# LoopV2_6.net
KiCad netlist of a schematic drawn in EAGLE
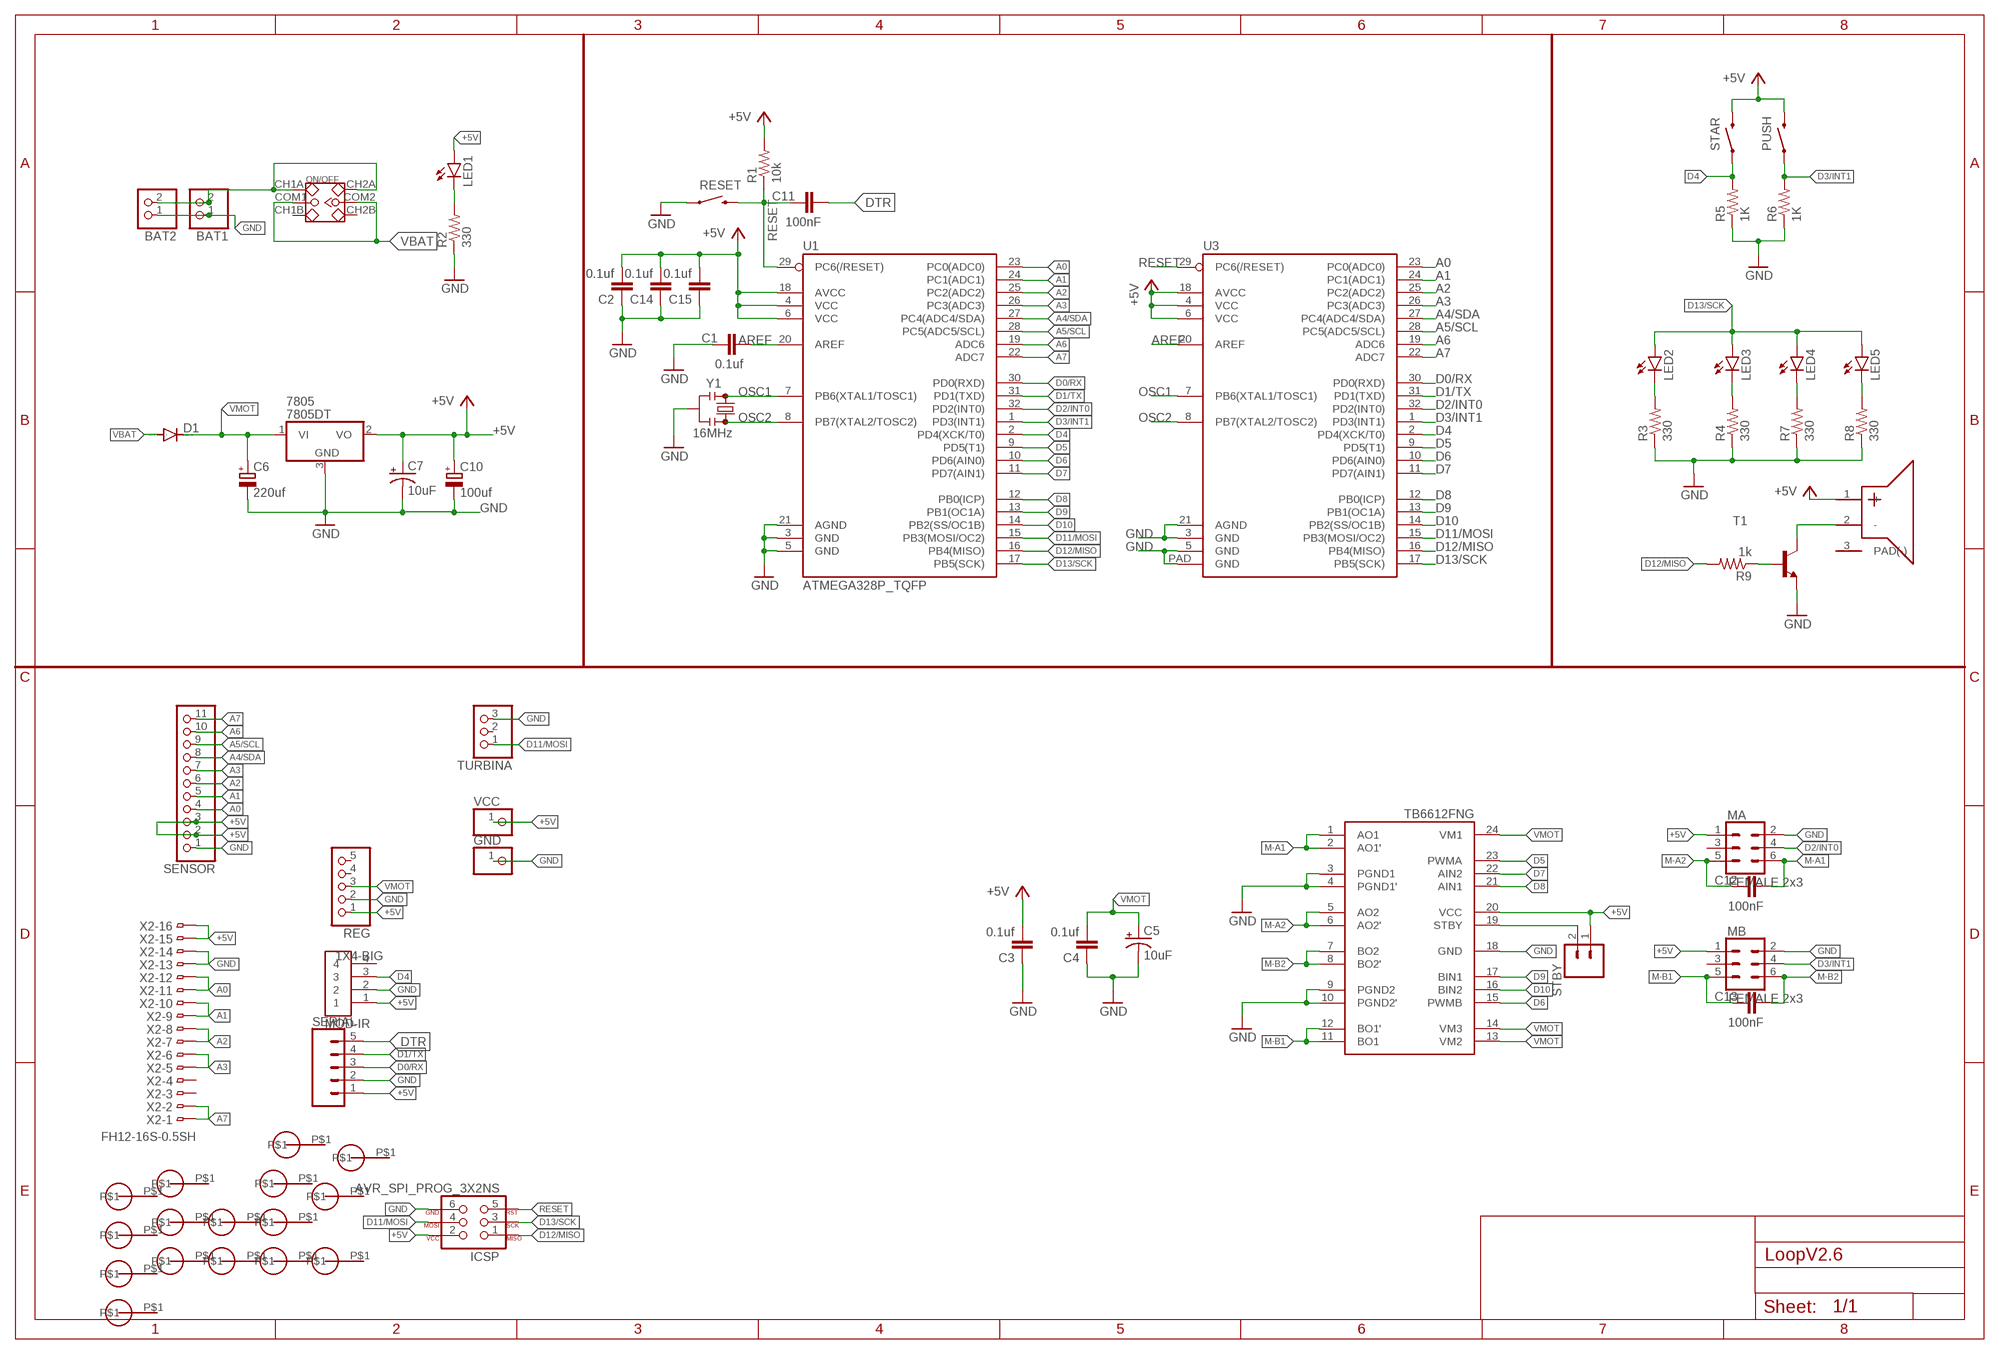
[diagram p0: schematic, sheet 1]

(export (version "E")
  (design (tool "Eeschema 10.0.6"))
  (components
    (comp (ref "7805")
      (value "7805DT")
      (footprint "eagle-import:TO252")
      (libsource (lib "eagle-import") (part "78DT05"))
    )
    (comp (ref "BAT1")
      (value "PINHD-1X2")
      (footprint "eagle-import:1X02")
      (libsource (lib "eagle-import") (part "PINHD-1X2"))
    )
    (comp (ref "BAT2")
      (value "PINHD-1X2")
      (footprint "eagle-import:1X02")
      (libsource (lib "eagle-import") (part "PINHD-1X2"))
    )
    (comp (ref "C1")
      (value "0.1uf")
      (footprint "eagle-import:C0805K")
      (libsource (lib "eagle-import") (part "C-EUC0805K"))
    )
    (comp (ref "C2")
      (value "0.1uf")
      (footprint "eagle-import:C0805K")
      (libsource (lib "eagle-import") (part "C-EUC0805K"))
    )
    (comp (ref "C3")
      (value "0.1uf")
      (footprint "eagle-import:C0805K")
      (libsource (lib "eagle-import") (part "C-EUC0805K"))
    )
    (comp (ref "C4")
      (value "0.1uf")
      (footprint "eagle-import:C0805K")
      (libsource (lib "eagle-import") (part "C-EUC0805K"))
    )
    (comp (ref "C5")
      (value "10uF")
      (footprint "eagle-import:EIA3216")
      (libsource (lib "eagle-import") (part "10UF-POLAR-EIA3216-16V-10%(TANT)"))
    )
    (comp (ref "C6")
      (value "220uf")
      (footprint "eagle-import:175TMP-0808")
      (libsource (lib "eagle-import") (part "CPOL-EU175TMP-0808"))
    )
    (comp (ref "C7")
      (value "10uF")
      (footprint "eagle-import:EIA3216")
      (libsource (lib "eagle-import") (part "10UF-POLAR-EIA3216-16V-10%(TANT)"))
    )
    (comp (ref "C10")
      (value "100uf")
      (footprint "eagle-import:153CLV-0605")
      (libsource (lib "eagle-import") (part "CPOL-EU153CLV-0605"))
    )
    (comp (ref "C11")
      (value "100nF")
      (footprint "eagle-import:C0805K")
      (libsource (lib "eagle-import") (part "C-EUC0805K"))
    )
    (comp (ref "C12")
      (value "100nF")
      (footprint "eagle-import:C0805K")
      (libsource (lib "eagle-import") (part "C-EUC0805K"))
    )
    (comp (ref "C13")
      (value "100nF")
      (footprint "eagle-import:C0805K")
      (libsource (lib "eagle-import") (part "C-EUC0805K"))
    )
    (comp (ref "C14")
      (value "0.1uf")
      (footprint "eagle-import:C0805K")
      (libsource (lib "eagle-import") (part "C-EUC0805K"))
    )
    (comp (ref "C15")
      (value "0.1uf")
      (footprint "eagle-import:C0805K")
      (libsource (lib "eagle-import") (part "C-EUC0805K"))
    )
    (comp (ref "D1")
      (value "DIODE-DO214AA")
      (footprint "eagle-import:DO214AA")
      (libsource (lib "eagle-import") (part "DIODE-DO214AA"))
    )
    (comp (ref "GND")
      (value "PINHD-1X1CB")
      (footprint "eagle-import:1X01-CLEANBIG")
      (libsource (lib "eagle-import") (part "PINHD-1X1CB"))
    )
    (comp (ref "IC1")
      (value "TB6612FNG")
      (footprint "eagle-import:SSOP24")
      (libsource (lib "eagle-import") (part "TB6612FNG"))
    )
    (comp (ref "ICSP")
      (value "AVR_SPI_PROG_3X2NS")
      (footprint "eagle-import:2X3-NS")
      (libsource (lib "eagle-import") (part "AVR_SPI_PROG_3X2NS"))
    )
    (comp (ref "LED1")
      (value "LEDCHIPLED_0805")
      (footprint "eagle-import:CHIPLED_0805")
      (libsource (lib "eagle-import") (part "LEDCHIPLED_0805"))
    )
    (comp (ref "LED2")
      (value "LEDCHIPLED_0805")
      (footprint "eagle-import:CHIPLED_0805")
      (libsource (lib "eagle-import") (part "LEDCHIPLED_0805"))
    )
    (comp (ref "LED3")
      (value "LEDCHIPLED_0805")
      (footprint "eagle-import:CHIPLED_0805")
      (libsource (lib "eagle-import") (part "LEDCHIPLED_0805"))
    )
    (comp (ref "LED4")
      (value "LEDCHIPLED_0805")
      (footprint "eagle-import:CHIPLED_0805")
      (libsource (lib "eagle-import") (part "LEDCHIPLED_0805"))
    )
    (comp (ref "LED5")
      (value "LEDCHIPLED_0805")
      (footprint "eagle-import:CHIPLED_0805")
      (libsource (lib "eagle-import") (part "LEDCHIPLED_0805"))
    )
    (comp (ref "MA")
      (value "FEMALE 2x3")
      (footprint "eagle-import:2X3")
      (libsource (lib "eagle-import") (part "CONN_03X2FEMALE"))
    )
    (comp (ref "MB")
      (value "FEMALE 2x3")
      (footprint "eagle-import:2X3")
      (libsource (lib "eagle-import") (part "CONN_03X2FEMALE"))
    )
    (comp (ref "MOD-IR")
      (value "1X4-BIG")
      (footprint "eagle-import:1X04-BIG")
      (libsource (lib "eagle-import") (part "1X4-BIG"))
    )
    (comp (ref "ON/OFF")
      (value "SWITCH-8.53.5MM-THT")
      (footprint "eagle-import:SWITCH-8.5_3.5MM-THT")
      (fields (field (name "MPN") "MS-22D18 G2 ROHS"))
      (libsource (lib "eagle-import") (part "SWITCH-8.53.5MM-THT"))
    )
    (comp (ref "PUSH")
      (value "TESTING_SWITCH-MOMENTARY-2SMD")
      (footprint "eagle-import:TESTING_TACTILE_SWITCH_SMD")
      (libsource (lib "eagle-import") (part "TESTING_SWITCH-MOMENTARY-2SMD"))
    )
    (comp (ref "R1")
      (value "10k")
      (footprint "eagle-import:R0805")
      (libsource (lib "eagle-import") (part "R-US_R0805"))
    )
    (comp (ref "R2")
      (value "330")
      (footprint "eagle-import:R0805")
      (libsource (lib "eagle-import") (part "R-US_R0805"))
    )
    (comp (ref "R3")
      (value "330")
      (footprint "eagle-import:R0805")
      (libsource (lib "eagle-import") (part "R-US_R0805"))
    )
    (comp (ref "R4")
      (value "330")
      (footprint "eagle-import:R0805")
      (libsource (lib "eagle-import") (part "R-US_R0805"))
    )
    (comp (ref "R5")
      (value "1K")
      (footprint "eagle-import:R0805")
      (libsource (lib "eagle-import") (part "R-US_R0805"))
    )
    (comp (ref "R6")
      (value "1K")
      (footprint "eagle-import:R0805")
      (libsource (lib "eagle-import") (part "R-US_R0805"))
    )
    (comp (ref "R7")
      (value "330")
      (footprint "eagle-import:R0805")
      (libsource (lib "eagle-import") (part "R-US_R0805"))
    )
    (comp (ref "R8")
      (value "330")
      (footprint "eagle-import:R0805")
      (libsource (lib "eagle-import") (part "R-US_R0805"))
    )
    (comp (ref "R9")
      (value "1k")
      (footprint "eagle-import:R0805")
      (libsource (lib "eagle-import") (part "R-US_R0805"))
    )
    (comp (ref "REG")
      (value "PINHD-1X5")
      (footprint "eagle-import:1X05")
      (libsource (lib "eagle-import") (part "PINHD-1X5"))
    )
    (comp (ref "RESET")
      (value "TESTING_SWITCH-MOMENTARY-2SMD")
      (footprint "eagle-import:TESTING_TACTILE_SWITCH_SMD")
      (libsource (lib "eagle-import") (part "TESTING_SWITCH-MOMENTARY-2SMD"))
    )
    (comp (ref "SENSOR")
      (value "PINHD-1X11")
      (footprint "eagle-import:1X11")
      (libsource (lib "eagle-import") (part "PINHD-1X11"))
    )
    (comp (ref "SERIAL")
      (value "CONN_05")
      (footprint "eagle-import:1X05")
      (libsource (lib "eagle-import") (part "CONN_05"))
    )
    (comp (ref "STAR")
      (value "TESTING_SWITCH-MOMENTARY-2SMD")
      (footprint "eagle-import:TESTING_TACTILE_SWITCH_SMD")
      (libsource (lib "eagle-import") (part "TESTING_SWITCH-MOMENTARY-2SMD"))
    )
    (comp (ref "STBY")
      (value "CONN_02")
      (footprint "eagle-import:1X02")
      (libsource (lib "eagle-import") (part "CONN_02"))
    )
    (comp (ref "T1")
      (value "-NPN-SOT23-EBC")
      (footprint "eagle-import:SOT23-EBC")
      (libsource (lib "eagle-import") (part "-NPN-SOT23-EBC"))
    )
    (comp (ref "TURBINA")
      (value "PINHD-1X3")
      (footprint "eagle-import:1X03")
      (libsource (lib "eagle-import") (part "PINHD-1X3"))
    )
    (comp (ref "U$4")
      (value "PAD2")
      (footprint "eagle-import:PAD-2.2MM")
      (libsource (lib "eagle-import") (part "PAD2"))
    )
    (comp (ref "U$5")
      (value "PAD2")
      (footprint "eagle-import:PAD-2.2MM")
      (libsource (lib "eagle-import") (part "PAD2"))
    )
    (comp (ref "U$6")
      (value "PAD2")
      (footprint "eagle-import:PAD-2.2MM")
      (libsource (lib "eagle-import") (part "PAD2"))
    )
    (comp (ref "U$7")
      (value "PAD2")
      (footprint "eagle-import:PAD-2.2MM")
      (libsource (lib "eagle-import") (part "PAD2"))
    )
    (comp (ref "U$8")
      (value "PAD2")
      (footprint "eagle-import:PAD-2.2MM")
      (libsource (lib "eagle-import") (part "PAD2"))
    )
    (comp (ref "U$9")
      (value "PAD2")
      (footprint "eagle-import:PAD-2.2MM")
      (libsource (lib "eagle-import") (part "PAD2"))
    )
    (comp (ref "U$10")
      (value "PAD2")
      (footprint "eagle-import:PAD-2.2MM")
      (libsource (lib "eagle-import") (part "PAD2"))
    )
    (comp (ref "U$11")
      (value "PAD2")
      (footprint "eagle-import:PAD-2.2MM")
      (libsource (lib "eagle-import") (part "PAD2"))
    )
    (comp (ref "U$12")
      (value "PAD2")
      (footprint "eagle-import:PAD-2.2MM")
      (libsource (lib "eagle-import") (part "PAD2"))
    )
    (comp (ref "U$13")
      (value "PAD2")
      (footprint "eagle-import:PAD-2.2MM")
      (libsource (lib "eagle-import") (part "PAD2"))
    )
    (comp (ref "U$14")
      (value "PAD2")
      (footprint "eagle-import:PAD-2.2MM")
      (libsource (lib "eagle-import") (part "PAD2"))
    )
    (comp (ref "U$15")
      (value "PAD2")
      (footprint "eagle-import:PAD-2.2MM")
      (libsource (lib "eagle-import") (part "PAD2"))
    )
    (comp (ref "U$16")
      (value "BUZZER-KLJ-5030")
      (footprint "eagle-import:BUZZERSMD")
      (libsource (lib "eagle-import") (part "BUZZER-KLJ-5030"))
    )
    (comp (ref "U$17")
      (value "PAD2")
      (footprint "eagle-import:PAD-2.2MM")
      (libsource (lib "eagle-import") (part "PAD2"))
    )
    (comp (ref "U$18")
      (value "PAD2")
      (footprint "eagle-import:PAD-2.2MM")
      (libsource (lib "eagle-import") (part "PAD2"))
    )
    (comp (ref "U$19")
      (value "PAD2")
      (footprint "eagle-import:PAD-2.2MM")
      (libsource (lib "eagle-import") (part "PAD2"))
    )
    (comp (ref "U$20")
      (value "PAD2")
      (footprint "eagle-import:PAD-2.2MM")
      (libsource (lib "eagle-import") (part "PAD2"))
    )
    (comp (ref "U1")
      (value "ATMEGA328P_TQFP")
      (footprint "eagle-import:TQFP32-08")
      (libsource (lib "eagle-import") (part "ATMEGA328P_TQFP"))
    )
    (comp (ref "U3")
      (value "ATMEGA328P_MLFMLF32")
      (footprint "eagle-import:MLF32-PAD")
      (libsource (lib "eagle-import") (part "ATMEGA328P_MLFMLF32"))
    )
    (comp (ref "VCC")
      (value "PINHD-1X1CB")
      (footprint "eagle-import:1X01-CLEANBIG")
      (libsource (lib "eagle-import") (part "PINHD-1X1CB"))
    )
    (comp (ref "X2")
      (value "FH12-16S-0.5SH")
      (footprint "eagle-import:FH12-16S-0.5SH")
      (fields (field (name "MPN") "FH12-16S-0.5SH(55)"))
      (libsource (lib "eagle-import") (part "FH12-16S-0.5SH"))
    )
    (comp (ref "Y1")
      (value "16MHz")
      (footprint "eagle-import:RESONATOR-SMD-3.2X1.3")
      (libsource (lib "eagle-import") (part "RESONATOR-16MHZSMD_3.2X1.3"))
    )
  )
  (nets
    (net (code "1") (name "+5V") (class "Default")
      (node (ref "7805") (pin "2") (pinfunction "VO_2") (pintype "passive"))
      (node (ref "C10") (pin "+") (pinfunction "+_+") (pintype "passive"))
      (node (ref "C14") (pin "2") (pinfunction "2_2") (pintype "passive"))
      (node (ref "C15") (pin "2") (pinfunction "2_2") (pintype "passive"))
      (node (ref "C2") (pin "2") (pinfunction "2_2") (pintype "passive"))
      (node (ref "C3") (pin "2") (pinfunction "2_2") (pintype "passive"))
      (node (ref "C7") (pin "+") (pinfunction "+_+") (pintype "passive"))
      (node (ref "IC1") (pin "20") (pinfunction "VCC_20") (pintype "power_in"))
      (node (ref "ICSP") (pin "2") (pinfunction "2_2") (pintype "passive"))
      (node (ref "LED1") (pin "A") (pinfunction "A_A") (pintype "passive"))
      (node (ref "MA") (pin "1") (pinfunction "1_1") (pintype "bidirectional"))
      (node (ref "MB") (pin "1") (pinfunction "1_1") (pintype "bidirectional"))
      (node (ref "MOD-IR") (pin "1") (pinfunction "1_1") (pintype "bidirectional"))
      (node (ref "PUSH") (pin "3") (pinfunction "2_3") (pintype "passive"))
      (node (ref "R1") (pin "2") (pinfunction "2_2") (pintype "passive"))
      (node (ref "REG") (pin "1") (pinfunction "1_1") (pintype "passive"))
      (node (ref "SENSOR") (pin "2") (pinfunction "2_2") (pintype "passive"))
      (node (ref "SENSOR") (pin "3") (pinfunction "3_3") (pintype "passive"))
      (node (ref "SERIAL") (pin "1") (pinfunction "1_1") (pintype "passive"))
      (node (ref "STAR") (pin "3") (pinfunction "2_3") (pintype "passive"))
      (node (ref "STBY") (pin "1") (pinfunction "1_1") (pintype "passive"))
      (node (ref "U$16") (pin "1") (pinfunction "+_1") (pintype "bidirectional"))
      (node (ref "U1") (pin "18") (pinfunction "AVCC_18") (pintype "bidirectional"))
      (node (ref "U1") (pin "4") (pinfunction "VCC_4") (pintype "bidirectional"))
      (node (ref "U1") (pin "6") (pinfunction "VCC_6") (pintype "bidirectional"))
      (node (ref "U3") (pin "18") (pinfunction "AVCC_18") (pintype "bidirectional"))
      (node (ref "U3") (pin "4") (pinfunction "VCC_4") (pintype "bidirectional"))
      (node (ref "U3") (pin "6") (pinfunction "VCC_6") (pintype "bidirectional"))
      (node (ref "VCC") (pin "1") (pinfunction "1_1") (pintype "passive"))
      (node (ref "X2") (pin "15") (pinfunction "1_15") (pintype "passive"))
      (node (ref "X2") (pin "16") (pinfunction "1_16") (pintype "passive"))
    )
    (net (code "2") (name "/AREF") (class "Default")
      (node (ref "C1") (pin "2") (pinfunction "2_2") (pintype "passive"))
      (node (ref "U1") (pin "20") (pinfunction "AREF_20") (pintype "bidirectional"))
      (node (ref "U3") (pin "20") (pinfunction "AREF_20") (pintype "bidirectional"))
    )
    (net (code "3") (name "/OSC1") (class "Default")
      (node (ref "U1") (pin "7") (pinfunction "PB6(XTAL1/TOSC1)_7") (pintype "bidirectional"))
      (node (ref "U3") (pin "7") (pinfunction "PB6(XTAL1/TOSC1)_7") (pintype "bidirectional"))
      (node (ref "Y1") (pin "1") (pinfunction "1_1") (pintype "passive"))
    )
    (net (code "4") (name "/OSC2") (class "Default")
      (node (ref "U1") (pin "8") (pinfunction "PB7(XTAL2/TOSC2)_8") (pintype "bidirectional"))
      (node (ref "U3") (pin "8") (pinfunction "PB7(XTAL2/TOSC2)_8") (pintype "bidirectional"))
      (node (ref "Y1") (pin "3") (pinfunction "3_3") (pintype "passive"))
    )
    (net (code "5") (name "A0") (class "Default")
      (node (ref "SENSOR") (pin "4") (pinfunction "4_4") (pintype "passive"))
      (node (ref "U1") (pin "23") (pinfunction "PC0(ADC0)_23") (pintype "bidirectional"))
      (node (ref "U3") (pin "23") (pinfunction "PC0(ADC0)_23") (pintype "bidirectional"))
      (node (ref "X2") (pin "11") (pinfunction "1_11") (pintype "passive"))
      (node (ref "X2") (pin "12") (pinfunction "1_12") (pintype "passive"))
    )
    (net (code "6") (name "A1") (class "Default")
      (node (ref "SENSOR") (pin "5") (pinfunction "5_5") (pintype "passive"))
      (node (ref "U1") (pin "24") (pinfunction "PC1(ADC1)_24") (pintype "bidirectional"))
      (node (ref "U3") (pin "24") (pinfunction "PC1(ADC1)_24") (pintype "bidirectional"))
      (node (ref "X2") (pin "10") (pinfunction "1_10") (pintype "passive"))
      (node (ref "X2") (pin "9") (pinfunction "1_9") (pintype "passive"))
    )
    (net (code "7") (name "A2") (class "Default")
      (node (ref "SENSOR") (pin "6") (pinfunction "6_6") (pintype "passive"))
      (node (ref "U1") (pin "25") (pinfunction "PC2(ADC2)_25") (pintype "bidirectional"))
      (node (ref "U3") (pin "25") (pinfunction "PC2(ADC2)_25") (pintype "bidirectional"))
      (node (ref "X2") (pin "7") (pinfunction "1_7") (pintype "passive"))
      (node (ref "X2") (pin "8") (pinfunction "1_8") (pintype "passive"))
    )
    (net (code "8") (name "A3") (class "Default")
      (node (ref "SENSOR") (pin "7") (pinfunction "7_7") (pintype "passive"))
      (node (ref "U1") (pin "26") (pinfunction "PC3(ADC3)_26") (pintype "bidirectional"))
      (node (ref "U3") (pin "26") (pinfunction "PC3(ADC3)_26") (pintype "bidirectional"))
      (node (ref "X2") (pin "5") (pinfunction "1_5") (pintype "passive"))
      (node (ref "X2") (pin "6") (pinfunction "1_6") (pintype "passive"))
    )
    (net (code "9") (name "A4{slash}SDA") (class "Default")
      (node (ref "SENSOR") (pin "8") (pinfunction "8_8") (pintype "passive"))
      (node (ref "U1") (pin "27") (pinfunction "PC4(ADC4/SDA)_27") (pintype "bidirectional"))
      (node (ref "U3") (pin "27") (pinfunction "PC4(ADC4/SDA)_27") (pintype "bidirectional"))
    )
    (net (code "10") (name "A5{slash}SCL") (class "Default")
      (node (ref "SENSOR") (pin "9") (pinfunction "9_9") (pintype "passive"))
      (node (ref "U1") (pin "28") (pinfunction "PC5(ADC5/SCL)_28") (pintype "bidirectional"))
      (node (ref "U3") (pin "28") (pinfunction "PC5(ADC5/SCL)_28") (pintype "bidirectional"))
    )
    (net (code "11") (name "A6") (class "Default")
      (node (ref "SENSOR") (pin "10") (pinfunction "10_10") (pintype "passive"))
      (node (ref "U1") (pin "19") (pinfunction "ADC6_19") (pintype "bidirectional"))
      (node (ref "U3") (pin "19") (pinfunction "ADC6_19") (pintype "bidirectional"))
    )
    (net (code "12") (name "A7") (class "Default")
      (node (ref "SENSOR") (pin "11") (pinfunction "11_11") (pintype "passive"))
      (node (ref "U1") (pin "22") (pinfunction "ADC7_22") (pintype "bidirectional"))
      (node (ref "U3") (pin "22") (pinfunction "ADC7_22") (pintype "bidirectional"))
      (node (ref "X2") (pin "1") (pinfunction "1_1") (pintype "passive"))
      (node (ref "X2") (pin "2") (pinfunction "1_2") (pintype "passive"))
    )
    (net (code "13") (name "D0{slash}RX") (class "Default")
      (node (ref "SERIAL") (pin "3") (pinfunction "3_3") (pintype "passive"))
      (node (ref "U1") (pin "30") (pinfunction "PD0(RXD)_30") (pintype "bidirectional"))
      (node (ref "U3") (pin "30") (pinfunction "PD0(RXD)_30") (pintype "bidirectional"))
    )
    (net (code "14") (name "D1{slash}TX") (class "Default")
      (node (ref "SERIAL") (pin "4") (pinfunction "4_4") (pintype "passive"))
      (node (ref "U1") (pin "31") (pinfunction "PD1(TXD)_31") (pintype "bidirectional"))
      (node (ref "U3") (pin "31") (pinfunction "PD1(TXD)_31") (pintype "bidirectional"))
    )
    (net (code "15") (name "D2{slash}INT0") (class "Default")
      (node (ref "MA") (pin "4") (pinfunction "4_4") (pintype "bidirectional"))
      (node (ref "U1") (pin "32") (pinfunction "PD2(INT0)_32") (pintype "bidirectional"))
      (node (ref "U3") (pin "32") (pinfunction "PD2(INT0)_32") (pintype "bidirectional"))
    )
    (net (code "16") (name "D3{slash}INT1") (class "Default")
      (node (ref "MB") (pin "4") (pinfunction "4_4") (pintype "bidirectional"))
      (node (ref "PUSH") (pin "1") (pinfunction "1_1") (pintype "passive"))
      (node (ref "R6") (pin "2") (pinfunction "2_2") (pintype "passive"))
      (node (ref "U1") (pin "1") (pinfunction "PD3(INT1)_1") (pintype "bidirectional"))
      (node (ref "U3") (pin "1") (pinfunction "PD3(INT1)_1") (pintype "bidirectional"))
    )
    (net (code "17") (name "D4") (class "Default")
      (node (ref "MOD-IR") (pin "3") (pinfunction "3_3") (pintype "bidirectional"))
      (node (ref "R5") (pin "2") (pinfunction "2_2") (pintype "passive"))
      (node (ref "STAR") (pin "1") (pinfunction "1_1") (pintype "passive"))
      (node (ref "U1") (pin "2") (pinfunction "PD4(XCK/T0)_2") (pintype "bidirectional"))
      (node (ref "U3") (pin "2") (pinfunction "PD4(XCK/T0)_2") (pintype "bidirectional"))
    )
    (net (code "18") (name "D5") (class "Default")
      (node (ref "IC1") (pin "23") (pinfunction "PWMA_23") (pintype "input"))
      (node (ref "U1") (pin "9") (pinfunction "PD5(T1)_9") (pintype "bidirectional"))
      (node (ref "U3") (pin "9") (pinfunction "PD5(T1)_9") (pintype "bidirectional"))
    )
    (net (code "19") (name "D6") (class "Default")
      (node (ref "IC1") (pin "15") (pinfunction "PWMB_15") (pintype "input"))
      (node (ref "U1") (pin "10") (pinfunction "PD6(AIN0)_10") (pintype "bidirectional"))
      (node (ref "U3") (pin "10") (pinfunction "PD6(AIN0)_10") (pintype "bidirectional"))
    )
    (net (code "20") (name "D7") (class "Default")
      (node (ref "IC1") (pin "22") (pinfunction "AIN2_22") (pintype "input"))
      (node (ref "U1") (pin "11") (pinfunction "PD7(AIN1)_11") (pintype "bidirectional"))
      (node (ref "U3") (pin "11") (pinfunction "PD7(AIN1)_11") (pintype "bidirectional"))
    )
    (net (code "21") (name "D8") (class "Default")
      (node (ref "IC1") (pin "21") (pinfunction "AIN1_21") (pintype "input"))
      (node (ref "U1") (pin "12") (pinfunction "PB0(ICP)_12") (pintype "bidirectional"))
      (node (ref "U3") (pin "12") (pinfunction "PB0(ICP)_12") (pintype "bidirectional"))
    )
    (net (code "22") (name "D9") (class "Default")
      (node (ref "IC1") (pin "17") (pinfunction "BIN1_17") (pintype "input"))
      (node (ref "U1") (pin "13") (pinfunction "PB1(OC1A)_13") (pintype "bidirectional"))
      (node (ref "U3") (pin "13") (pinfunction "PB1(OC1A)_13") (pintype "bidirectional"))
    )
    (net (code "23") (name "D10") (class "Default")
      (node (ref "IC1") (pin "16") (pinfunction "BIN2_16") (pintype "input"))
      (node (ref "U1") (pin "14") (pinfunction "PB2(SS/OC1B)_14") (pintype "bidirectional"))
      (node (ref "U3") (pin "14") (pinfunction "PB2(SS/OC1B)_14") (pintype "bidirectional"))
    )
    (net (code "24") (name "D11{slash}MOSI") (class "Default")
      (node (ref "ICSP") (pin "4") (pinfunction "4_4") (pintype "passive"))
      (node (ref "TURBINA") (pin "1") (pinfunction "1_1") (pintype "passive"))
      (node (ref "U1") (pin "15") (pinfunction "PB3(MOSI/OC2)_15") (pintype "bidirectional"))
      (node (ref "U3") (pin "15") (pinfunction "PB3(MOSI/OC2)_15") (pintype "bidirectional"))
    )
    (net (code "25") (name "D12{slash}MISO") (class "Default")
      (node (ref "ICSP") (pin "1") (pinfunction "1_1") (pintype "passive"))
      (node (ref "R9") (pin "2") (pinfunction "2_2") (pintype "passive"))
      (node (ref "U1") (pin "16") (pinfunction "PB4(MISO)_16") (pintype "bidirectional"))
      (node (ref "U3") (pin "16") (pinfunction "PB4(MISO)_16") (pintype "bidirectional"))
    )
    (net (code "26") (name "D13{slash}SCK") (class "Default")
      (node (ref "ICSP") (pin "3") (pinfunction "3_3") (pintype "passive"))
      (node (ref "LED2") (pin "A") (pinfunction "A_A") (pintype "passive"))
      (node (ref "LED3") (pin "A") (pinfunction "A_A") (pintype "passive"))
      (node (ref "LED4") (pin "A") (pinfunction "A_A") (pintype "passive"))
      (node (ref "LED5") (pin "A") (pinfunction "A_A") (pintype "passive"))
      (node (ref "U1") (pin "17") (pinfunction "PB5(SCK)_17") (pintype "bidirectional"))
      (node (ref "U3") (pin "17") (pinfunction "PB5(SCK)_17") (pintype "bidirectional"))
    )
    (net (code "27") (name "DTR") (class "Default")
      (node (ref "C11") (pin "2") (pinfunction "2_2") (pintype "passive"))
      (node (ref "SERIAL") (pin "5") (pinfunction "5_5") (pintype "passive"))
    )
    (net (code "28") (name "GND") (class "Default")
      (node (ref "7805") (pin "3") (pinfunction "GND_3") (pintype "passive"))
      (node (ref "BAT1") (pin "1") (pinfunction "1_1") (pintype "passive"))
      (node (ref "BAT2") (pin "1") (pinfunction "1_1") (pintype "passive"))
      (node (ref "C1") (pin "1") (pinfunction "1_1") (pintype "passive"))
      (node (ref "C10") (pin "-") (pinfunction "-_-") (pintype "passive"))
      (node (ref "C14") (pin "1") (pinfunction "1_1") (pintype "passive"))
      (node (ref "C15") (pin "1") (pinfunction "1_1") (pintype "passive"))
      (node (ref "C2") (pin "1") (pinfunction "1_1") (pintype "passive"))
      (node (ref "C3") (pin "1") (pinfunction "1_1") (pintype "passive"))
      (node (ref "C4") (pin "1") (pinfunction "1_1") (pintype "passive"))
      (node (ref "C5") (pin "-") (pinfunction "-_-") (pintype "passive"))
      (node (ref "C6") (pin "-") (pinfunction "-_-") (pintype "passive"))
      (node (ref "C7") (pin "-") (pinfunction "-_-") (pintype "passive"))
      (node (ref "GND") (pin "1") (pinfunction "1_1") (pintype "passive"))
      (node (ref "IC1") (pin "10") (pinfunction "PGND2'_10") (pintype "power_in"))
      (node (ref "IC1") (pin "18") (pinfunction "GND_18") (pintype "power_in"))
      (node (ref "IC1") (pin "3") (pinfunction "PGND1_3") (pintype "power_in"))
      (node (ref "IC1") (pin "4") (pinfunction "PGND1'_4") (pintype "power_in"))
      (node (ref "IC1") (pin "9") (pinfunction "PGND2_9") (pintype "power_in"))
      (node (ref "ICSP") (pin "6") (pinfunction "6_6") (pintype "passive"))
      (node (ref "MA") (pin "2") (pinfunction "2_2") (pintype "bidirectional"))
      (node (ref "MB") (pin "2") (pinfunction "2_2") (pintype "bidirectional"))
      (node (ref "MOD-IR") (pin "2") (pinfunction "2_2") (pintype "bidirectional"))
      (node (ref "R2") (pin "1") (pinfunction "1_1") (pintype "passive"))
      (node (ref "R3") (pin "1") (pinfunction "1_1") (pintype "passive"))
      (node (ref "R4") (pin "1") (pinfunction "1_1") (pintype "passive"))
      (node (ref "R5") (pin "1") (pinfunction "1_1") (pintype "passive"))
      (node (ref "R6") (pin "1") (pinfunction "1_1") (pintype "passive"))
      (node (ref "R7") (pin "1") (pinfunction "1_1") (pintype "passive"))
      (node (ref "R8") (pin "1") (pinfunction "1_1") (pintype "passive"))
      (node (ref "REG") (pin "2") (pinfunction "2_2") (pintype "passive"))
      (node (ref "RESET") (pin "1") (pinfunction "1_1") (pintype "passive"))
      (node (ref "SENSOR") (pin "1") (pinfunction "1_1") (pintype "passive"))
      (node (ref "SERIAL") (pin "2") (pinfunction "2_2") (pintype "passive"))
      (node (ref "T1") (pin "E") (pinfunction "E_E") (pintype "passive"))
      (node (ref "TURBINA") (pin "3") (pinfunction "3_3") (pintype "passive"))
      (node (ref "U1") (pin "21") (pinfunction "AGND_21") (pintype "bidirectional"))
      (node (ref "U1") (pin "3") (pinfunction "GND_3") (pintype "bidirectional"))
      (node (ref "U1") (pin "5") (pinfunction "GND_5") (pintype "bidirectional"))
      (node (ref "U3") (pin "21") (pinfunction "AGND_21") (pintype "bidirectional"))
      (node (ref "U3") (pin "3") (pinfunction "GND_3") (pintype "bidirectional"))
      (node (ref "U3") (pin "5") (pinfunction "GND_5") (pintype "bidirectional"))
      (node (ref "U3") (pin "PAD") (pinfunction "GND_PAD") (pintype "bidirectional"))
      (node (ref "X2") (pin "13") (pinfunction "1_13") (pintype "passive"))
      (node (ref "X2") (pin "14") (pinfunction "1_14") (pintype "passive"))
      (node (ref "Y1") (pin "2") (pinfunction "2_2") (pintype "passive"))
    )
    (net (code "29") (name "M-A1") (class "Default")
      (node (ref "C12") (pin "2") (pinfunction "2_2") (pintype "passive"))
      (node (ref "IC1") (pin "1") (pinfunction "AO1_1") (pintype "output"))
      (node (ref "IC1") (pin "2") (pinfunction "AO1'_2") (pintype "output"))
      (node (ref "MA") (pin "6") (pinfunction "6_6") (pintype "bidirectional"))
    )
    (net (code "30") (name "M-A2") (class "Default")
      (node (ref "C12") (pin "1") (pinfunction "1_1") (pintype "passive"))
      (node (ref "IC1") (pin "5") (pinfunction "AO2_5") (pintype "output"))
      (node (ref "IC1") (pin "6") (pinfunction "AO2'_6") (pintype "output"))
      (node (ref "MA") (pin "5") (pinfunction "5_5") (pintype "bidirectional"))
    )
    (net (code "31") (name "M-B1") (class "Default")
      (node (ref "C13") (pin "1") (pinfunction "1_1") (pintype "passive"))
      (node (ref "IC1") (pin "11") (pinfunction "BO1_11") (pintype "output"))
      (node (ref "IC1") (pin "12") (pinfunction "BO1'_12") (pintype "output"))
      (node (ref "MB") (pin "5") (pinfunction "5_5") (pintype "bidirectional"))
    )
    (net (code "32") (name "M-B2") (class "Default")
      (node (ref "C13") (pin "2") (pinfunction "2_2") (pintype "passive"))
      (node (ref "IC1") (pin "7") (pinfunction "BO2_7") (pintype "output"))
      (node (ref "IC1") (pin "8") (pinfunction "BO2'_8") (pintype "output"))
      (node (ref "MB") (pin "6") (pinfunction "6_6") (pintype "bidirectional"))
    )
    (net (code "33") (name "Net-(BAT1-Pad2)") (class "Default")
      (node (ref "BAT1") (pin "2") (pinfunction "2_2") (pintype "passive"))
      (node (ref "BAT2") (pin "2") (pinfunction "2_2") (pintype "passive"))
      (node (ref "ON/OFF") (pin "CH1A") (pinfunction "CH1A_CH1A") (pintype "bidirectional"))
      (node (ref "ON/OFF") (pin "CH2A") (pinfunction "CH2A_CH2A") (pintype "bidirectional"))
    )
    (net (code "34") (name "Net-(IC1-STBY)") (class "Default")
      (node (ref "IC1") (pin "19") (pinfunction "STBY_19") (pintype "input"))
      (node (ref "STBY") (pin "2") (pinfunction "2_2") (pintype "passive"))
    )
    (net (code "35") (name "Net-(LED1-PadC)") (class "Default")
      (node (ref "LED1") (pin "C") (pinfunction "C_C") (pintype "passive"))
      (node (ref "R2") (pin "2") (pinfunction "2_2") (pintype "passive"))
    )
    (net (code "36") (name "Net-(LED2-PadC)") (class "Default")
      (node (ref "LED2") (pin "C") (pinfunction "C_C") (pintype "passive"))
      (node (ref "R3") (pin "2") (pinfunction "2_2") (pintype "passive"))
    )
    (net (code "37") (name "Net-(LED3-PadC)") (class "Default")
      (node (ref "LED3") (pin "C") (pinfunction "C_C") (pintype "passive"))
      (node (ref "R4") (pin "2") (pinfunction "2_2") (pintype "passive"))
    )
    (net (code "38") (name "Net-(LED4-PadC)") (class "Default")
      (node (ref "LED4") (pin "C") (pinfunction "C_C") (pintype "passive"))
      (node (ref "R7") (pin "2") (pinfunction "2_2") (pintype "passive"))
    )
    (net (code "39") (name "Net-(LED5-PadC)") (class "Default")
      (node (ref "LED5") (pin "C") (pinfunction "C_C") (pintype "passive"))
      (node (ref "R8") (pin "2") (pinfunction "2_2") (pintype "passive"))
    )
    (net (code "40") (name "Net-(R9-Pad1)") (class "Default")
      (node (ref "R9") (pin "1") (pinfunction "1_1") (pintype "passive"))
      (node (ref "T1") (pin "B") (pinfunction "B_B") (pintype "passive"))
    )
    (net (code "41") (name "Net-(U$16--)") (class "Default")
      (node (ref "T1") (pin "C") (pinfunction "C_C") (pintype "passive"))
      (node (ref "U$16") (pin "2") (pinfunction "-_2") (pintype "bidirectional"))
    )
    (net (code "42") (name "RESET") (class "Default")
      (node (ref "C11") (pin "1") (pinfunction "1_1") (pintype "passive"))
      (node (ref "ICSP") (pin "5") (pinfunction "5_5") (pintype "passive"))
      (node (ref "R1") (pin "1") (pinfunction "1_1") (pintype "passive"))
      (node (ref "RESET") (pin "3") (pinfunction "2_3") (pintype "passive"))
      (node (ref "U1") (pin "29") (pinfunction "PC6(/RESET)_29") (pintype "bidirectional"))
      (node (ref "U3") (pin "29") (pinfunction "PC6(/RESET)_29") (pintype "bidirectional"))
    )
    (net (code "43") (name "VBAT") (class "Default")
      (node (ref "D1") (pin "A") (pinfunction "A_A") (pintype "passive"))
      (node (ref "ON/OFF") (pin "COM1") (pinfunction "COM1_COM1") (pintype "bidirectional"))
      (node (ref "ON/OFF") (pin "COM2") (pinfunction "COM2_COM2") (pintype "bidirectional"))
    )
    (net (code "44") (name "VMOT") (class "Default")
      (node (ref "7805") (pin "1") (pinfunction "VI_1") (pintype "input"))
      (node (ref "C4") (pin "2") (pinfunction "2_2") (pintype "passive"))
      (node (ref "C5") (pin "+") (pinfunction "+_+") (pintype "passive"))
      (node (ref "C6") (pin "+") (pinfunction "+_+") (pintype "passive"))
      (node (ref "D1") (pin "C") (pinfunction "C_C") (pintype "passive"))
      (node (ref "IC1") (pin "13") (pinfunction "VM2_13") (pintype "power_in"))
      (node (ref "IC1") (pin "14") (pinfunction "VM3_14") (pintype "power_in"))
      (node (ref "IC1") (pin "24") (pinfunction "VM1_24") (pintype "power_in"))
      (node (ref "REG") (pin "3") (pinfunction "3_3") (pintype "passive"))
    )
    (net (code "45") (name "unconnected-(MA-Pad3)") (class "Default")
      (node (ref "MA") (pin "3") (pinfunction "3_3") (pintype "bidirectional"))
    )
    (net (code "46") (name "unconnected-(MB-Pad3)") (class "Default")
      (node (ref "MB") (pin "3") (pinfunction "3_3") (pintype "bidirectional"))
    )
    (net (code "47") (name "unconnected-(MOD-IR-Pad4)") (class "Default")
      (node (ref "MOD-IR") (pin "4") (pinfunction "4_4") (pintype "bidirectional"))
    )
    (net (code "48") (name "unconnected-(ON/OFF-PadCH1B)") (class "Default")
      (node (ref "ON/OFF") (pin "CH1B") (pinfunction "CH1B_CH1B") (pintype "bidirectional"))
    )
    (net (code "49") (name "unconnected-(ON/OFF-PadCH2B)") (class "Default")
      (node (ref "ON/OFF") (pin "CH2B") (pinfunction "CH2B_CH2B") (pintype "bidirectional"))
    )
    (net (code "50") (name "unconnected-(REG-Pad4)") (class "Default")
      (node (ref "REG") (pin "4") (pinfunction "4_4") (pintype "passive"))
    )
    (net (code "51") (name "unconnected-(REG-Pad5)") (class "Default")
      (node (ref "REG") (pin "5") (pinfunction "5_5") (pintype "passive"))
    )
    (net (code "52") (name "unconnected-(TURBINA-Pad2)") (class "Default")
      (node (ref "TURBINA") (pin "2") (pinfunction "2_2") (pintype "passive"))
    )
    (net (code "53") (name "unconnected-(U$4-PadP$1)") (class "Default")
      (node (ref "U$4") (pin "P$1") (pinfunction "P$1_P$1") (pintype "bidirectional"))
    )
    (net (code "54") (name "unconnected-(U$5-PadP$1)") (class "Default")
      (node (ref "U$5") (pin "P$1") (pinfunction "P$1_P$1") (pintype "bidirectional"))
    )
    (net (code "55") (name "unconnected-(U$6-PadP$1)") (class "Default")
      (node (ref "U$6") (pin "P$1") (pinfunction "P$1_P$1") (pintype "bidirectional"))
    )
    (net (code "56") (name "unconnected-(U$7-PadP$1)") (class "Default")
      (node (ref "U$7") (pin "P$1") (pinfunction "P$1_P$1") (pintype "bidirectional"))
    )
    (net (code "57") (name "unconnected-(U$8-PadP$1)") (class "Default")
      (node (ref "U$8") (pin "P$1") (pinfunction "P$1_P$1") (pintype "bidirectional"))
    )
    (net (code "58") (name "unconnected-(U$9-PadP$1)") (class "Default")
      (node (ref "U$9") (pin "P$1") (pinfunction "P$1_P$1") (pintype "bidirectional"))
    )
    (net (code "59") (name "unconnected-(U$10-PadP$1)") (class "Default")
      (node (ref "U$10") (pin "P$1") (pinfunction "P$1_P$1") (pintype "bidirectional"))
    )
    (net (code "60") (name "unconnected-(U$11-PadP$1)") (class "Default")
      (node (ref "U$11") (pin "P$1") (pinfunction "P$1_P$1") (pintype "bidirectional"))
    )
    (net (code "61") (name "unconnected-(U$12-PadP$1)") (class "Default")
      (node (ref "U$12") (pin "P$1") (pinfunction "P$1_P$1") (pintype "bidirectional"))
    )
    (net (code "62") (name "unconnected-(U$13-PadP$1)") (class "Default")
      (node (ref "U$13") (pin "P$1") (pinfunction "P$1_P$1") (pintype "bidirectional"))
    )
    (net (code "63") (name "unconnected-(U$14-PadP$1)") (class "Default")
      (node (ref "U$14") (pin "P$1") (pinfunction "P$1_P$1") (pintype "bidirectional"))
    )
    (net (code "64") (name "unconnected-(U$15-PadP$1)") (class "Default")
      (node (ref "U$15") (pin "P$1") (pinfunction "P$1_P$1") (pintype "bidirectional"))
    )
    (net (code "65") (name "unconnected-(U$16-PAD(-)-Pad3)") (class "Default")
      (node (ref "U$16") (pin "3") (pinfunction "PAD(-)_3") (pintype "bidirectional"))
    )
    (net (code "66") (name "unconnected-(U$17-PadP$1)") (class "Default")
      (node (ref "U$17") (pin "P$1") (pinfunction "P$1_P$1") (pintype "bidirectional"))
    )
    (net (code "67") (name "unconnected-(U$18-PadP$1)") (class "Default")
      (node (ref "U$18") (pin "P$1") (pinfunction "P$1_P$1") (pintype "bidirectional"))
    )
    (net (code "68") (name "unconnected-(U$19-PadP$1)") (class "Default")
      (node (ref "U$19") (pin "P$1") (pinfunction "P$1_P$1") (pintype "bidirectional"))
    )
    (net (code "69") (name "unconnected-(U$20-PadP$1)") (class "Default")
      (node (ref "U$20") (pin "P$1") (pinfunction "P$1_P$1") (pintype "bidirectional"))
    )
    (net (code "70") (name "unconnected-(X2J-1-Pad3)") (class "Default")
      (node (ref "X2") (pin "3") (pinfunction "1_3") (pintype "passive"))
    )
    (net (code "71") (name "unconnected-(X2K-1-Pad4)") (class "Default")
      (node (ref "X2") (pin "4") (pinfunction "1_4") (pintype "passive"))
    )
  )
)
